# poppy.net
KiCad netlist of a schematic drawn in EAGLE
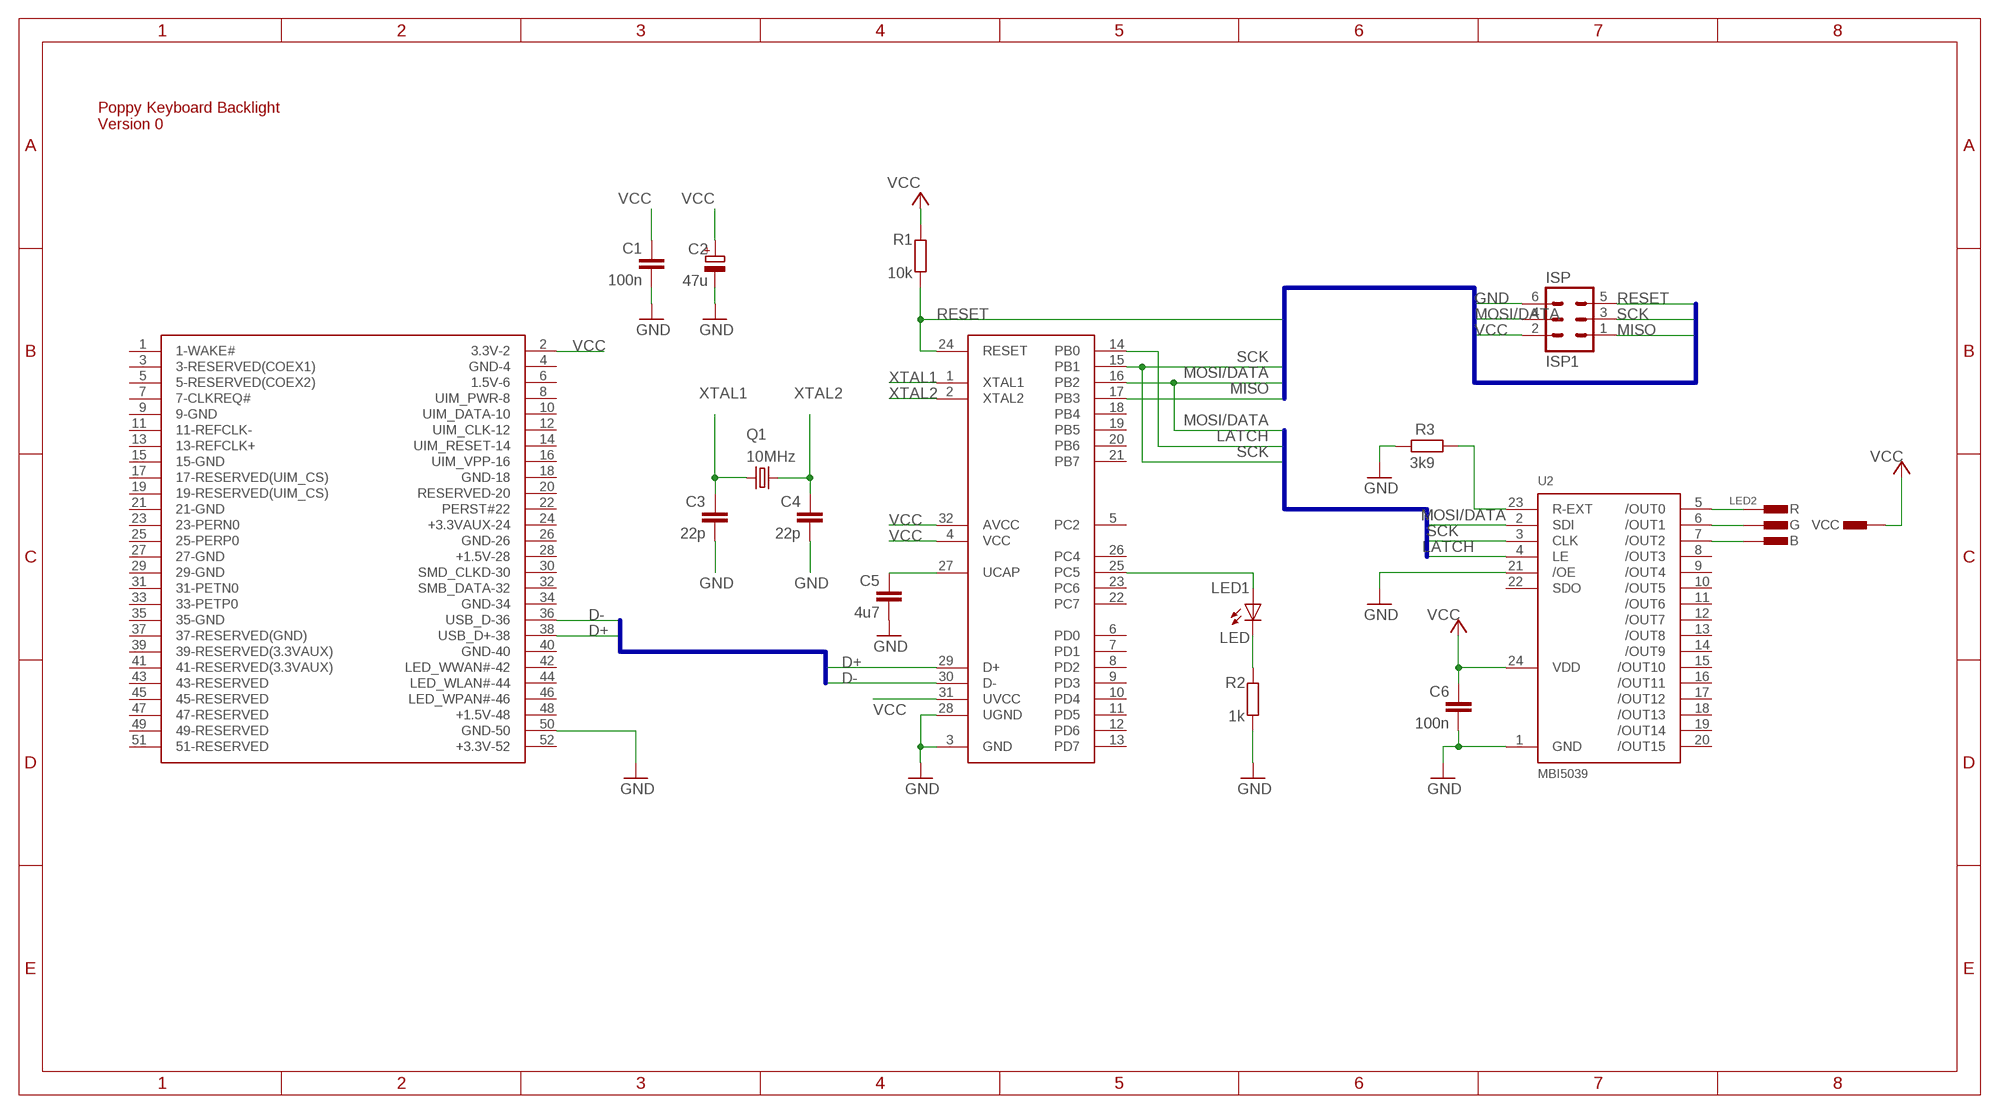
[diagram p0: schematic, sheet 1]

(export (version "E")
  (design (tool "Eeschema 10.0.6"))
  (components
    (comp (ref "C1")
      (value "100n")
      (footprint "eagle-import:C4532")
      (libsource (lib "eagle-import") (part "C-EUC4532"))
    )
    (comp (ref "C2")
      (value "47u")
      (footprint "eagle-import:150CLZ-0810")
      (libsource (lib "eagle-import") (part "CPOL-EU150CLZ-0810"))
    )
    (comp (ref "C3")
      (value "22p")
      (footprint "eagle-import:C1206K")
      (libsource (lib "eagle-import") (part "C-EUC1206K"))
    )
    (comp (ref "C4")
      (value "22p")
      (footprint "eagle-import:C1206K")
      (libsource (lib "eagle-import") (part "C-EUC1206K"))
    )
    (comp (ref "C5")
      (value "4u7")
      (footprint "eagle-import:C1206K")
      (libsource (lib "eagle-import") (part "C-EUC1206K"))
    )
    (comp (ref "C6")
      (value "100n")
      (footprint "eagle-import:C1206K")
      (libsource (lib "eagle-import") (part "C-EUC1206K"))
    )
    (comp (ref "EDGE")
      (value "FULL-MINI-PCI-E")
      (footprint "eagle-import:FULL-MINI-PCI-E")
      (libsource (lib "eagle-import") (part "FULL-MINI-PCI-E"))
    )
    (comp (ref "ISP")
      (value "ISP1")
      (footprint "eagle-import:MA03-2")
      (libsource (lib "eagle-import") (part "MA03-2"))
    )
    (comp (ref "LED1")
      (value "LED")
      (footprint "eagle-import:CHIPLED_0805")
      (libsource (lib "eagle-import") (part "LEDCHIPLED_0805"))
    )
    (comp (ref "LED2")
      (value "CON-RGB-LED-EXT")
      (footprint "eagle-import:CON-RGB-LED-TH-EXT")
      (libsource (lib "eagle-import") (part "CON-RGB-LED-EXT"))
    )
    (comp (ref "Q1")
      (value "10MHz")
      (footprint "eagle-import:CTS406")
      (libsource (lib "eagle-import") (part "CRYSTALCTS406"))
    )
    (comp (ref "R1")
      (value "10k")
      (footprint "eagle-import:R1206")
      (libsource (lib "eagle-import") (part "R-EU_R1206"))
    )
    (comp (ref "R2")
      (value "1k")
      (footprint "eagle-import:R1206")
      (libsource (lib "eagle-import") (part "R-EU_R1206"))
    )
    (comp (ref "R3")
      (value "3k9")
      (footprint "eagle-import:R1206")
      (libsource (lib "eagle-import") (part "R-EU_R1206"))
    )
    (comp (ref "U1")
      (value "ATUSB")
      (footprint "eagle-import:VQFP32")
      (libsource (lib "eagle-import") (part "AT90USB162"))
    )
    (comp (ref "U2")
      (value "MBI5039")
      (footprint "eagle-import:SOP24-300-1.00")
      (libsource (lib "eagle-import") (part "MBI5039SOP24-300-1.00"))
    )
  )
  (nets
    (net (code "1") (name "/D+") (class "Default")
      (node (ref "EDGE") (pin "38") (pinfunction "USB_D+-38_38") (pintype "bidirectional"))
      (node (ref "U1") (pin "29") (pinfunction "D+_29") (pintype "bidirectional"))
    )
    (net (code "2") (name "/D-") (class "Default")
      (node (ref "EDGE") (pin "36") (pinfunction "USB_D-36_36") (pintype "bidirectional"))
      (node (ref "U1") (pin "30") (pinfunction "D-_30") (pintype "bidirectional"))
    )
    (net (code "3") (name "/LATCH") (class "Default")
      (node (ref "U1") (pin "14") (pinfunction "PB0_14") (pintype "bidirectional"))
      (node (ref "U2") (pin "4") (pinfunction "LE_4") (pintype "bidirectional"))
    )
    (net (code "4") (name "/MISO") (class "Default")
      (node (ref "ISP") (pin "1") (pinfunction "1_1") (pintype "passive"))
      (node (ref "U1") (pin "17") (pinfunction "PB3_17") (pintype "bidirectional"))
    )
    (net (code "5") (name "/MOSI{slash}DATA") (class "Default")
      (node (ref "ISP") (pin "4") (pinfunction "4_4") (pintype "passive"))
      (node (ref "U1") (pin "16") (pinfunction "PB2_16") (pintype "bidirectional"))
      (node (ref "U2") (pin "2") (pinfunction "SDI_2") (pintype "bidirectional"))
    )
    (net (code "6") (name "/RESET") (class "Default")
      (node (ref "ISP") (pin "5") (pinfunction "5_5") (pintype "passive"))
      (node (ref "R1") (pin "1") (pinfunction "1_1") (pintype "passive"))
      (node (ref "U1") (pin "24") (pinfunction "RESET_24") (pintype "bidirectional"))
    )
    (net (code "7") (name "/SCK") (class "Default")
      (node (ref "ISP") (pin "3") (pinfunction "3_3") (pintype "passive"))
      (node (ref "U1") (pin "15") (pinfunction "PB1_15") (pintype "bidirectional"))
      (node (ref "U2") (pin "3") (pinfunction "CLK_3") (pintype "bidirectional"))
    )
    (net (code "8") (name "/XTAL1") (class "Default")
      (node (ref "C3") (pin "1") (pinfunction "1_1") (pintype "passive"))
      (node (ref "Q1") (pin "1") (pinfunction "1_1") (pintype "passive"))
      (node (ref "U1") (pin "1") (pinfunction "XTAL1_1") (pintype "bidirectional"))
    )
    (net (code "9") (name "/XTAL2") (class "Default")
      (node (ref "C4") (pin "1") (pinfunction "1_1") (pintype "passive"))
      (node (ref "Q1") (pin "3") (pinfunction "2_3") (pintype "passive"))
      (node (ref "U1") (pin "2") (pinfunction "XTAL2_2") (pintype "bidirectional"))
    )
    (net (code "10") (name "GND") (class "Default")
      (node (ref "C1") (pin "2") (pinfunction "2_2") (pintype "passive"))
      (node (ref "C2") (pin "-") (pinfunction "-_-") (pintype "passive"))
      (node (ref "C3") (pin "2") (pinfunction "2_2") (pintype "passive"))
      (node (ref "C4") (pin "2") (pinfunction "2_2") (pintype "passive"))
      (node (ref "C5") (pin "2") (pinfunction "2_2") (pintype "passive"))
      (node (ref "C6") (pin "2") (pinfunction "2_2") (pintype "passive"))
      (node (ref "EDGE") (pin "50") (pinfunction "GND-50_50") (pintype "bidirectional"))
      (node (ref "ISP") (pin "6") (pinfunction "6_6") (pintype "passive"))
      (node (ref "R2") (pin "1") (pinfunction "1_1") (pintype "passive"))
      (node (ref "R3") (pin "1") (pinfunction "1_1") (pintype "passive"))
      (node (ref "U1") (pin "28") (pinfunction "UGND_28") (pintype "bidirectional"))
      (node (ref "U1") (pin "3") (pinfunction "GND_3") (pintype "power_in"))
      (node (ref "U2") (pin "1") (pinfunction "GND_1") (pintype "bidirectional"))
      (node (ref "U2") (pin "21") (pinfunction "/OE_21") (pintype "bidirectional"))
    )
    (net (code "11") (name "Net-(LED1-PadC)") (class "Default")
      (node (ref "LED1") (pin "C") (pinfunction "C_C") (pintype "passive"))
      (node (ref "R2") (pin "2") (pinfunction "2_2") (pintype "passive"))
    )
    (net (code "12") (name "Net-(LED2-B)") (class "Default")
      (node (ref "LED2") (pin "1.B") (pinfunction "B_1.B") (pintype "bidirectional"))
      (node (ref "U2") (pin "7") (pinfunction "/OUT2_7") (pintype "bidirectional"))
    )
    (net (code "13") (name "Net-(LED2-G)") (class "Default")
      (node (ref "LED2") (pin "2.G") (pinfunction "G_2.G") (pintype "bidirectional"))
      (node (ref "U2") (pin "6") (pinfunction "/OUT1_6") (pintype "bidirectional"))
    )
    (net (code "14") (name "Net-(LED2-R)") (class "Default")
      (node (ref "LED2") (pin "3.R") (pinfunction "R_3.R") (pintype "bidirectional"))
      (node (ref "U2") (pin "5") (pinfunction "/OUT0_5") (pintype "bidirectional"))
    )
    (net (code "15") (name "Net-(U1-PC5)") (class "Default")
      (node (ref "LED1") (pin "A") (pinfunction "A_A") (pintype "passive"))
      (node (ref "U1") (pin "25") (pinfunction "PC5_25") (pintype "bidirectional"))
    )
    (net (code "16") (name "Net-(U1-UCAP)") (class "Default")
      (node (ref "C5") (pin "1") (pinfunction "1_1") (pintype "passive"))
      (node (ref "U1") (pin "27") (pinfunction "UCAP_27") (pintype "bidirectional"))
    )
    (net (code "17") (name "Net-(U2-R-EXT)") (class "Default")
      (node (ref "R3") (pin "2") (pinfunction "2_2") (pintype "passive"))
      (node (ref "U2") (pin "23") (pinfunction "R-EXT_23") (pintype "bidirectional"))
    )
    (net (code "18") (name "VCC") (class "Default")
      (node (ref "C1") (pin "1") (pinfunction "1_1") (pintype "passive"))
      (node (ref "C2") (pin "+") (pinfunction "+_+") (pintype "passive"))
      (node (ref "C6") (pin "1") (pinfunction "1_1") (pintype "passive"))
      (node (ref "EDGE") (pin "2") (pinfunction "3.3V-2_2") (pintype "bidirectional"))
      (node (ref "ISP") (pin "2") (pinfunction "2_2") (pintype "passive"))
      (node (ref "LED2") (pin "4.VCC") (pinfunction "VCC_4.VCC") (pintype "bidirectional"))
      (node (ref "R1") (pin "2") (pinfunction "2_2") (pintype "passive"))
      (node (ref "U1") (pin "31") (pinfunction "UVCC_31") (pintype "bidirectional"))
      (node (ref "U1") (pin "32") (pinfunction "AVCC_32") (pintype "bidirectional"))
      (node (ref "U1") (pin "4") (pinfunction "VCC_4") (pintype "power_in"))
      (node (ref "U2") (pin "24") (pinfunction "VDD_24") (pintype "bidirectional"))
    )
    (net (code "19") (name "unconnected-(EDGEA-+1.5V-28-Pad28)") (class "Default")
      (node (ref "EDGE") (pin "28") (pinfunction "+1.5V-28_28") (pintype "bidirectional"))
    )
    (net (code "20") (name "unconnected-(EDGEA-+1.5V-48-Pad48)") (class "Default")
      (node (ref "EDGE") (pin "48") (pinfunction "+1.5V-48_48") (pintype "bidirectional"))
    )
    (net (code "21") (name "unconnected-(EDGEA-+3.3V-52-Pad52)") (class "Default")
      (node (ref "EDGE") (pin "52") (pinfunction "+3.3V-52_52") (pintype "bidirectional"))
    )
    (net (code "22") (name "unconnected-(EDGEA-+3.3VAUX-24-Pad24)") (class "Default")
      (node (ref "EDGE") (pin "24") (pinfunction "+3.3VAUX-24_24") (pintype "bidirectional"))
    )
    (net (code "23") (name "unconnected-(EDGEA-1-WAKE#-Pad1)") (class "Default")
      (node (ref "EDGE") (pin "1") (pinfunction "1-WAKE#_1") (pintype "bidirectional"))
    )
    (net (code "24") (name "unconnected-(EDGEA-1.5V-6-Pad6)") (class "Default")
      (node (ref "EDGE") (pin "6") (pinfunction "1.5V-6_6") (pintype "bidirectional"))
    )
    (net (code "25") (name "unconnected-(EDGEA-3-RESERVED(COEX1)-Pad3)") (class "Default")
      (node (ref "EDGE") (pin "3") (pinfunction "3-RESERVED(COEX1)_3") (pintype "bidirectional"))
    )
    (net (code "26") (name "unconnected-(EDGEA-5-RESERVED(COEX2)-Pad5)") (class "Default")
      (node (ref "EDGE") (pin "5") (pinfunction "5-RESERVED(COEX2)_5") (pintype "bidirectional"))
    )
    (net (code "27") (name "unconnected-(EDGEA-7-CLKREQ#-Pad7)") (class "Default")
      (node (ref "EDGE") (pin "7") (pinfunction "7-CLKREQ#_7") (pintype "bidirectional"))
    )
    (net (code "28") (name "unconnected-(EDGEA-9-GND-Pad9)") (class "Default")
      (node (ref "EDGE") (pin "9") (pinfunction "9-GND_9") (pintype "bidirectional"))
    )
    (net (code "29") (name "unconnected-(EDGEA-11-REFCLK--Pad11)") (class "Default")
      (node (ref "EDGE") (pin "11") (pinfunction "11-REFCLK-_11") (pintype "bidirectional"))
    )
    (net (code "30") (name "unconnected-(EDGEA-13-REFCLK+-Pad13)") (class "Default")
      (node (ref "EDGE") (pin "13") (pinfunction "13-REFCLK+_13") (pintype "bidirectional"))
    )
    (net (code "31") (name "unconnected-(EDGEA-15-GND-Pad15)") (class "Default")
      (node (ref "EDGE") (pin "15") (pinfunction "15-GND_15") (pintype "bidirectional"))
    )
    (net (code "32") (name "unconnected-(EDGEA-17-RESERVED(UIM_CS)-Pad17)") (class "Default")
      (node (ref "EDGE") (pin "17") (pinfunction "17-RESERVED(UIM_CS)_17") (pintype "bidirectional"))
    )
    (net (code "33") (name "unconnected-(EDGEA-19-RESERVED(UIM_CS)-Pad19)") (class "Default")
      (node (ref "EDGE") (pin "19") (pinfunction "19-RESERVED(UIM_CS)_19") (pintype "bidirectional"))
    )
    (net (code "34") (name "unconnected-(EDGEA-21-GND-Pad21)") (class "Default")
      (node (ref "EDGE") (pin "21") (pinfunction "21-GND_21") (pintype "bidirectional"))
    )
    (net (code "35") (name "unconnected-(EDGEA-23-PERN0-Pad23)") (class "Default")
      (node (ref "EDGE") (pin "23") (pinfunction "23-PERN0_23") (pintype "bidirectional"))
    )
    (net (code "36") (name "unconnected-(EDGEA-25-PERP0-Pad25)") (class "Default")
      (node (ref "EDGE") (pin "25") (pinfunction "25-PERP0_25") (pintype "bidirectional"))
    )
    (net (code "37") (name "unconnected-(EDGEA-27-GND-Pad27)") (class "Default")
      (node (ref "EDGE") (pin "27") (pinfunction "27-GND_27") (pintype "bidirectional"))
    )
    (net (code "38") (name "unconnected-(EDGEA-29-GND-Pad29)") (class "Default")
      (node (ref "EDGE") (pin "29") (pinfunction "29-GND_29") (pintype "bidirectional"))
    )
    (net (code "39") (name "unconnected-(EDGEA-31-PETN0-Pad31)") (class "Default")
      (node (ref "EDGE") (pin "31") (pinfunction "31-PETN0_31") (pintype "bidirectional"))
    )
    (net (code "40") (name "unconnected-(EDGEA-33-PETP0-Pad33)") (class "Default")
      (node (ref "EDGE") (pin "33") (pinfunction "33-PETP0_33") (pintype "bidirectional"))
    )
    (net (code "41") (name "unconnected-(EDGEA-35-GND-Pad35)") (class "Default")
      (node (ref "EDGE") (pin "35") (pinfunction "35-GND_35") (pintype "bidirectional"))
    )
    (net (code "42") (name "unconnected-(EDGEA-37-RESERVED(GND)-Pad37)") (class "Default")
      (node (ref "EDGE") (pin "37") (pinfunction "37-RESERVED(GND)_37") (pintype "bidirectional"))
    )
    (net (code "43") (name "unconnected-(EDGEA-39-RESERVED(3.3VAUX)-Pad39)") (class "Default")
      (node (ref "EDGE") (pin "39") (pinfunction "39-RESERVED(3.3VAUX)_39") (pintype "bidirectional"))
    )
    (net (code "44") (name "unconnected-(EDGEA-41-RESERVED(3.3VAUX)-Pad41)") (class "Default")
      (node (ref "EDGE") (pin "41") (pinfunction "41-RESERVED(3.3VAUX)_41") (pintype "bidirectional"))
    )
    (net (code "45") (name "unconnected-(EDGEA-43-RESERVED-Pad43)") (class "Default")
      (node (ref "EDGE") (pin "43") (pinfunction "43-RESERVED_43") (pintype "bidirectional"))
    )
    (net (code "46") (name "unconnected-(EDGEA-45-RESERVED-Pad45)") (class "Default")
      (node (ref "EDGE") (pin "45") (pinfunction "45-RESERVED_45") (pintype "bidirectional"))
    )
    (net (code "47") (name "unconnected-(EDGEA-47-RESERVED-Pad47)") (class "Default")
      (node (ref "EDGE") (pin "47") (pinfunction "47-RESERVED_47") (pintype "bidirectional"))
    )
    (net (code "48") (name "unconnected-(EDGEA-49-RESERVED-Pad49)") (class "Default")
      (node (ref "EDGE") (pin "49") (pinfunction "49-RESERVED_49") (pintype "bidirectional"))
    )
    (net (code "49") (name "unconnected-(EDGEA-51-RESERVED-Pad51)") (class "Default")
      (node (ref "EDGE") (pin "51") (pinfunction "51-RESERVED_51") (pintype "bidirectional"))
    )
    (net (code "50") (name "unconnected-(EDGEA-GND-4-Pad4)") (class "Default")
      (node (ref "EDGE") (pin "4") (pinfunction "GND-4_4") (pintype "bidirectional"))
    )
    (net (code "51") (name "unconnected-(EDGEA-GND-18-Pad18)") (class "Default")
      (node (ref "EDGE") (pin "18") (pinfunction "GND-18_18") (pintype "bidirectional"))
    )
    (net (code "52") (name "unconnected-(EDGEA-GND-26-Pad26)") (class "Default")
      (node (ref "EDGE") (pin "26") (pinfunction "GND-26_26") (pintype "bidirectional"))
    )
    (net (code "53") (name "unconnected-(EDGEA-GND-34-Pad34)") (class "Default")
      (node (ref "EDGE") (pin "34") (pinfunction "GND-34_34") (pintype "bidirectional"))
    )
    (net (code "54") (name "unconnected-(EDGEA-GND-40-Pad40)") (class "Default")
      (node (ref "EDGE") (pin "40") (pinfunction "GND-40_40") (pintype "bidirectional"))
    )
    (net (code "55") (name "unconnected-(EDGEA-LED_WLAN#-44-Pad44)") (class "Default")
      (node (ref "EDGE") (pin "44") (pinfunction "LED_WLAN#-44_44") (pintype "bidirectional"))
    )
    (net (code "56") (name "unconnected-(EDGEA-LED_WPAN#-46-Pad46)") (class "Default")
      (node (ref "EDGE") (pin "46") (pinfunction "LED_WPAN#-46_46") (pintype "bidirectional"))
    )
    (net (code "57") (name "unconnected-(EDGEA-LED_WWAN#-42-Pad42)") (class "Default")
      (node (ref "EDGE") (pin "42") (pinfunction "LED_WWAN#-42_42") (pintype "bidirectional"))
    )
    (net (code "58") (name "unconnected-(EDGEA-PERST#22-Pad22)") (class "Default")
      (node (ref "EDGE") (pin "22") (pinfunction "PERST#22_22") (pintype "bidirectional"))
    )
    (net (code "59") (name "unconnected-(EDGEA-RESERVED-20-Pad20)") (class "Default")
      (node (ref "EDGE") (pin "20") (pinfunction "RESERVED-20_20") (pintype "bidirectional"))
    )
    (net (code "60") (name "unconnected-(EDGEA-SMB_DATA-32-Pad32)") (class "Default")
      (node (ref "EDGE") (pin "32") (pinfunction "SMB_DATA-32_32") (pintype "bidirectional"))
    )
    (net (code "61") (name "unconnected-(EDGEA-SMD_CLKD-30-Pad30)") (class "Default")
      (node (ref "EDGE") (pin "30") (pinfunction "SMD_CLKD-30_30") (pintype "bidirectional"))
    )
    (net (code "62") (name "unconnected-(EDGEA-UIM_CLK-12-Pad12)") (class "Default")
      (node (ref "EDGE") (pin "12") (pinfunction "UIM_CLK-12_12") (pintype "bidirectional"))
    )
    (net (code "63") (name "unconnected-(EDGEA-UIM_DATA-10-Pad10)") (class "Default")
      (node (ref "EDGE") (pin "10") (pinfunction "UIM_DATA-10_10") (pintype "bidirectional"))
    )
    (net (code "64") (name "unconnected-(EDGEA-UIM_PWR-8-Pad8)") (class "Default")
      (node (ref "EDGE") (pin "8") (pinfunction "UIM_PWR-8_8") (pintype "bidirectional"))
    )
    (net (code "65") (name "unconnected-(EDGEA-UIM_RESET-14-Pad14)") (class "Default")
      (node (ref "EDGE") (pin "14") (pinfunction "UIM_RESET-14_14") (pintype "bidirectional"))
    )
    (net (code "66") (name "unconnected-(EDGEA-UIM_VPP-16-Pad16)") (class "Default")
      (node (ref "EDGE") (pin "16") (pinfunction "UIM_VPP-16_16") (pintype "bidirectional"))
    )
    (net (code "67") (name "unconnected-(U1-PB4-Pad18)") (class "Default")
      (node (ref "U1") (pin "18") (pinfunction "PB4_18") (pintype "bidirectional"))
    )
    (net (code "68") (name "unconnected-(U1-PB5-Pad19)") (class "Default")
      (node (ref "U1") (pin "19") (pinfunction "PB5_19") (pintype "bidirectional"))
    )
    (net (code "69") (name "unconnected-(U1-PB6-Pad20)") (class "Default")
      (node (ref "U1") (pin "20") (pinfunction "PB6_20") (pintype "bidirectional"))
    )
    (net (code "70") (name "unconnected-(U1-PB7-Pad21)") (class "Default")
      (node (ref "U1") (pin "21") (pinfunction "PB7_21") (pintype "bidirectional"))
    )
    (net (code "71") (name "unconnected-(U1-PC2-Pad5)") (class "Default")
      (node (ref "U1") (pin "5") (pinfunction "PC2_5") (pintype "bidirectional"))
    )
    (net (code "72") (name "unconnected-(U1-PC4-Pad26)") (class "Default")
      (node (ref "U1") (pin "26") (pinfunction "PC4_26") (pintype "bidirectional"))
    )
    (net (code "73") (name "unconnected-(U1-PC6-Pad23)") (class "Default")
      (node (ref "U1") (pin "23") (pinfunction "PC6_23") (pintype "bidirectional"))
    )
    (net (code "74") (name "unconnected-(U1-PC7-Pad22)") (class "Default")
      (node (ref "U1") (pin "22") (pinfunction "PC7_22") (pintype "bidirectional"))
    )
    (net (code "75") (name "unconnected-(U1-PD0-Pad6)") (class "Default")
      (node (ref "U1") (pin "6") (pinfunction "PD0_6") (pintype "bidirectional"))
    )
    (net (code "76") (name "unconnected-(U1-PD1-Pad7)") (class "Default")
      (node (ref "U1") (pin "7") (pinfunction "PD1_7") (pintype "bidirectional"))
    )
    (net (code "77") (name "unconnected-(U1-PD2-Pad8)") (class "Default")
      (node (ref "U1") (pin "8") (pinfunction "PD2_8") (pintype "bidirectional"))
    )
    (net (code "78") (name "unconnected-(U1-PD3-Pad9)") (class "Default")
      (node (ref "U1") (pin "9") (pinfunction "PD3_9") (pintype "bidirectional"))
    )
    (net (code "79") (name "unconnected-(U1-PD4-Pad10)") (class "Default")
      (node (ref "U1") (pin "10") (pinfunction "PD4_10") (pintype "bidirectional"))
    )
    (net (code "80") (name "unconnected-(U1-PD5-Pad11)") (class "Default")
      (node (ref "U1") (pin "11") (pinfunction "PD5_11") (pintype "bidirectional"))
    )
    (net (code "81") (name "unconnected-(U1-PD6-Pad12)") (class "Default")
      (node (ref "U1") (pin "12") (pinfunction "PD6_12") (pintype "bidirectional"))
    )
    (net (code "82") (name "unconnected-(U1-PD7-Pad13)") (class "Default")
      (node (ref "U1") (pin "13") (pinfunction "PD7_13") (pintype "bidirectional"))
    )
    (net (code "83") (name "unconnected-(U2-SDO-Pad22)") (class "Default")
      (node (ref "U2") (pin "22") (pinfunction "SDO_22") (pintype "bidirectional"))
    )
    (net (code "84") (name "unconnected-(U2-{slash}OUT3-Pad8)") (class "Default")
      (node (ref "U2") (pin "8") (pinfunction "/OUT3_8") (pintype "bidirectional"))
    )
    (net (code "85") (name "unconnected-(U2-{slash}OUT4-Pad9)") (class "Default")
      (node (ref "U2") (pin "9") (pinfunction "/OUT4_9") (pintype "bidirectional"))
    )
    (net (code "86") (name "unconnected-(U2-{slash}OUT5-Pad10)") (class "Default")
      (node (ref "U2") (pin "10") (pinfunction "/OUT5_10") (pintype "bidirectional"))
    )
    (net (code "87") (name "unconnected-(U2-{slash}OUT6-Pad11)") (class "Default")
      (node (ref "U2") (pin "11") (pinfunction "/OUT6_11") (pintype "bidirectional"))
    )
    (net (code "88") (name "unconnected-(U2-{slash}OUT7-Pad12)") (class "Default")
      (node (ref "U2") (pin "12") (pinfunction "/OUT7_12") (pintype "bidirectional"))
    )
    (net (code "89") (name "unconnected-(U2-{slash}OUT8-Pad13)") (class "Default")
      (node (ref "U2") (pin "13") (pinfunction "/OUT8_13") (pintype "bidirectional"))
    )
    (net (code "90") (name "unconnected-(U2-{slash}OUT9-Pad14)") (class "Default")
      (node (ref "U2") (pin "14") (pinfunction "/OUT9_14") (pintype "bidirectional"))
    )
    (net (code "91") (name "unconnected-(U2-{slash}OUT10-Pad15)") (class "Default")
      (node (ref "U2") (pin "15") (pinfunction "/OUT10_15") (pintype "bidirectional"))
    )
    (net (code "92") (name "unconnected-(U2-{slash}OUT11-Pad16)") (class "Default")
      (node (ref "U2") (pin "16") (pinfunction "/OUT11_16") (pintype "bidirectional"))
    )
    (net (code "93") (name "unconnected-(U2-{slash}OUT12-Pad17)") (class "Default")
      (node (ref "U2") (pin "17") (pinfunction "/OUT12_17") (pintype "bidirectional"))
    )
    (net (code "94") (name "unconnected-(U2-{slash}OUT13-Pad18)") (class "Default")
      (node (ref "U2") (pin "18") (pinfunction "/OUT13_18") (pintype "bidirectional"))
    )
    (net (code "95") (name "unconnected-(U2-{slash}OUT14-Pad19)") (class "Default")
      (node (ref "U2") (pin "19") (pinfunction "/OUT14_19") (pintype "bidirectional"))
    )
    (net (code "96") (name "unconnected-(U2-{slash}OUT15-Pad20)") (class "Default")
      (node (ref "U2") (pin "20") (pinfunction "/OUT15_20") (pintype "bidirectional"))
    )
  )
)
